# schema.net
KiCad netlist of a schematic drawn in Altium Designer
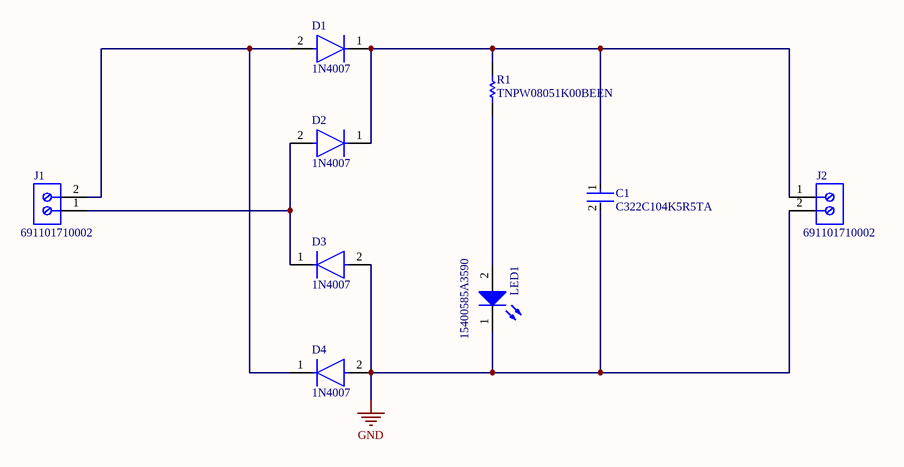
[diagram p0: schema.SchDoc]

(export (version "E")
  (design (tool "Eeschema 10.0.6"))
  (components
    (comp (ref "C1")
      (value "C322C104K5R5TA")
      (footprint "FP-C322C104K5R5TA-MFG")
      (description "CAP CER 0.1UF 50V X7R RADIAL")
      (fields (field (name "TOLERANCE") "10%") (field (name "VOLTAGE") "50V"))
      (libsource (lib "Altium Content Vault") (part "b4654b650e69147ec39a6b967a45e02"))
    )
    (comp (ref "D1")
      (value "1N4007")
      (footprint "FP-1N4007-MFG")
      (description "Rectifier diode 1000 V 1 A DO-41, ,")
      (fields
        (field (name "MANUFACTURER") "Diotec")
        (field (name "OCTOPART") "https://octopart.com/1n4007-diotec-4040411")
      )
      (libsource (lib "Altium Content Vault") (part "d7152d700b627762746794eb795d46e"))
    )
    (comp (ref "D2")
      (value "1N4007")
      (footprint "FP-1N4007-MFG")
      (description "Rectifier diode 1000 V 1 A DO-41, ,")
      (fields
        (field (name "MANUFACTURER") "Diotec")
        (field (name "OCTOPART") "https://octopart.com/1n4007-diotec-4040411")
      )
      (libsource (lib "Altium Content Vault") (part "d7152d700b627762746794eb795d46e"))
    )
    (comp (ref "D3")
      (value "1N4007")
      (footprint "FP-1N4007-MFG")
      (description "Rectifier diode 1000 V 1 A DO-41, ,")
      (fields
        (field (name "MANUFACTURER") "Diotec")
        (field (name "OCTOPART") "https://octopart.com/1n4007-diotec-4040411")
      )
      (libsource (lib "Altium Content Vault") (part "d7152d700b627762746794eb795d46e"))
    )
    (comp (ref "D4")
      (value "1N4007")
      (footprint "FP-1N4007-MFG")
      (description "Rectifier diode 1000 V 1 A DO-41, ,")
      (fields
        (field (name "MANUFACTURER") "Diotec")
        (field (name "OCTOPART") "https://octopart.com/1n4007-diotec-4040411")
      )
      (libsource (lib "Altium Content Vault") (part "d7152d700b627762746794eb795d46e"))
    )
    (comp (ref "J1")
      (value "691101710002")
      (footprint "691101710002")
      (description "Conn Terminal Block 2 POS 5mm Solder ST Thru-Hole 16A Box")
      (fields (field (name "VOLTAGE") "250V"))
      (libsource (lib "Altium Content Vault") (part "TBL - 1R - 02P - Screw"))
    )
    (comp (ref "J2")
      (value "691101710002")
      (footprint "691101710002")
      (description "Conn Terminal Block 2 POS 5mm Solder ST Thru-Hole 16A Box")
      (fields (field (name "VOLTAGE") "250V"))
      (libsource (lib "Altium Content Vault") (part "TBL - 1R - 02P - Screw"))
    )
    (comp (ref "LED1")
      (value "15400585A3590")
      (footprint "WL-TIRW_D5.8H8.6")
      (description "WL-TIRW THT Infrared Round Waterclear")
      (libsource (lib "Altium Content Vault") (part "LED_Infrared_2A-1K"))
    )
    (comp (ref "R1")
      (value "TNPW08051K00BEEN")
      (footprint "RESC2013X55X40LL15T20")
      (fields (field (name "MANUFACTURER") "Vishay Dale"))
      (libsource (lib "Altium Content Vault") (part "RES"))
    )
  )
  (nets
    (net (code "1") (name "GND") (class "Default")
      (node (ref "C1") (pin "2") (pinfunction "2_2") (pintype "passive"))
      (node (ref "D3") (pin "2") (pinfunction "A_2") (pintype "passive"))
      (node (ref "D4") (pin "2") (pinfunction "A_2") (pintype "passive"))
      (node (ref "J2") (pin "2") (pinfunction "2_2") (pintype "passive"))
      (node (ref "LED1") (pin "1") (pinfunction "K_1") (pintype "passive"))
    )
    (net (code "2") (name "Net-(D1-A)") (class "Default")
      (node (ref "D1") (pin "2") (pinfunction "A_2") (pintype "passive"))
      (node (ref "D4") (pin "1") (pinfunction "C_1") (pintype "passive"))
      (node (ref "J1") (pin "2") (pinfunction "2_2") (pintype "passive"))
    )
    (net (code "3") (name "Net-(D1-C)") (class "Default")
      (node (ref "C1") (pin "1") (pinfunction "1_1") (pintype "passive"))
      (node (ref "D1") (pin "1") (pinfunction "C_1") (pintype "passive"))
      (node (ref "D2") (pin "1") (pinfunction "C_1") (pintype "passive"))
      (node (ref "J2") (pin "1") (pinfunction "1_1") (pintype "passive"))
      (node (ref "R1") (pin "2") (pinfunction "2_2") (pintype "passive"))
    )
    (net (code "4") (name "Net-(D2-A)") (class "Default")
      (node (ref "D2") (pin "2") (pinfunction "A_2") (pintype "passive"))
      (node (ref "D3") (pin "1") (pinfunction "C_1") (pintype "passive"))
      (node (ref "J1") (pin "1") (pinfunction "1_1") (pintype "passive"))
    )
    (net (code "5") (name "Net-(LED1-A)") (class "Default")
      (node (ref "LED1") (pin "2") (pinfunction "A_2") (pintype "passive"))
      (node (ref "R1") (pin "1") (pinfunction "1_1") (pintype "passive"))
    )
  )
)
